# AVR_Programmer.net
KiCad netlist of a schematic drawn in Altium Designer
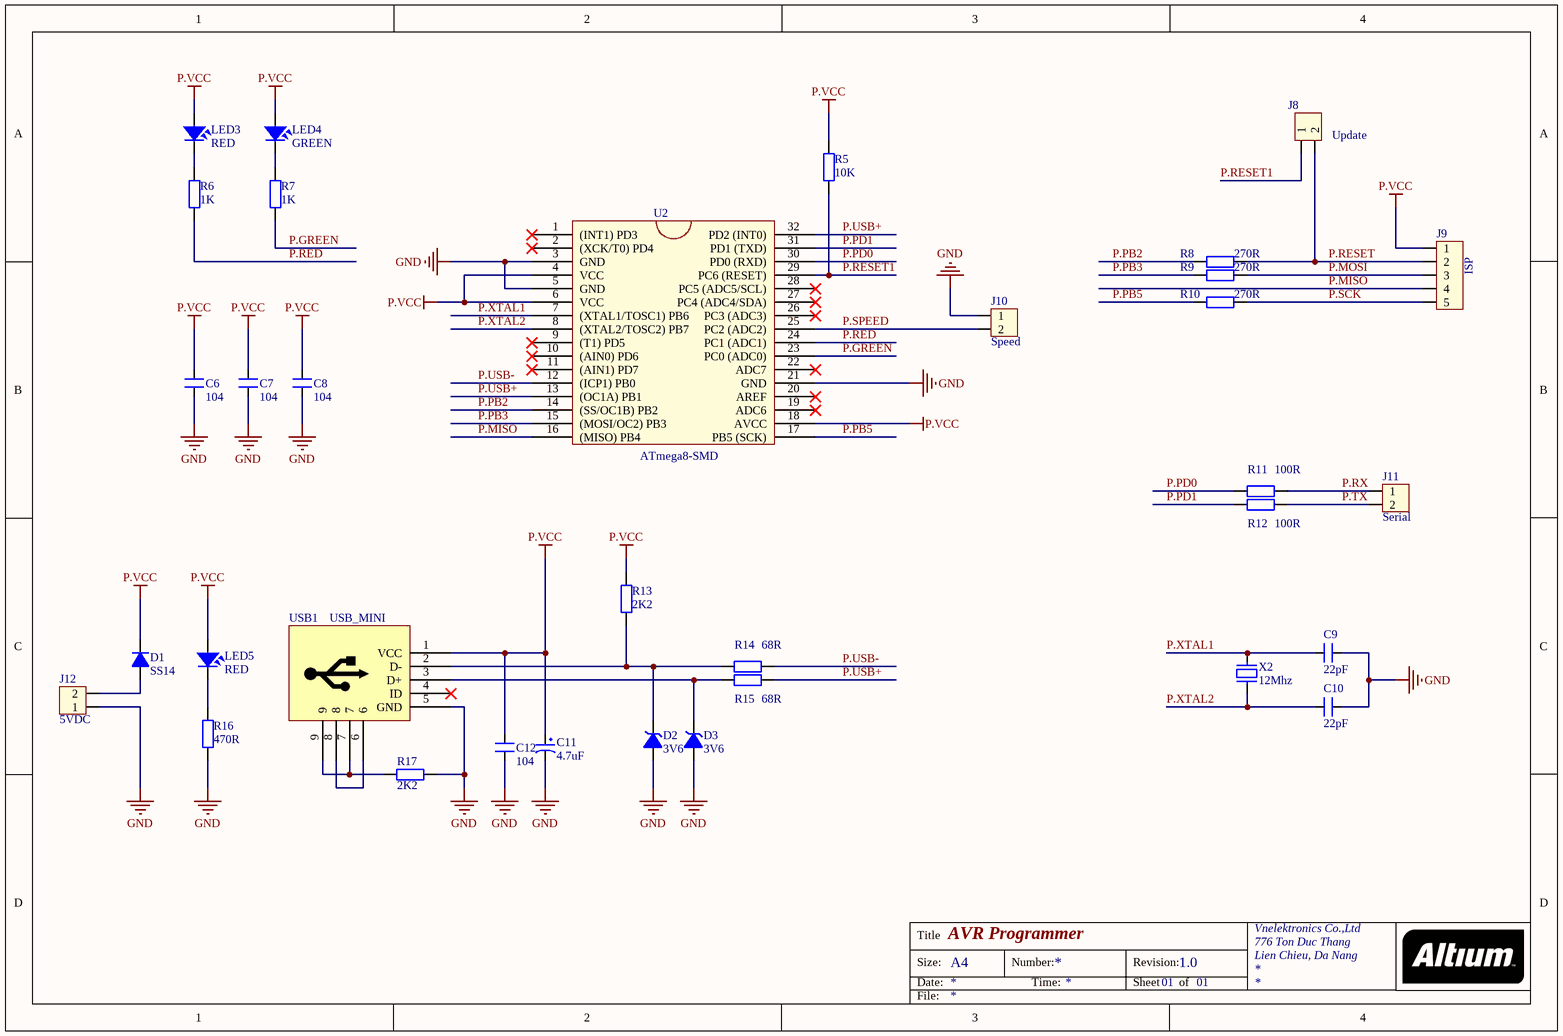
[diagram p0: AVR Programmer.SchDoc]

(export (version "E")
  (design (tool "Eeschema 10.0.6"))
  (components
    (comp (ref "C6")
      (value "104")
      (footprint "C0805")
      (description "Cap np 104 => 105pF")
      (libsource (lib "syhaunguyen") (part "CN2"))
    )
    (comp (ref "C7")
      (value "104")
      (footprint "C0805")
      (description "Cap np 104 => 105pF")
      (libsource (lib "syhaunguyen") (part "CN2"))
    )
    (comp (ref "C8")
      (value "104")
      (footprint "C0805")
      (description "Cap np 104 => 105pF")
      (libsource (lib "syhaunguyen") (part "CN2"))
    )
    (comp (ref "C9")
      (value "22pF")
      (footprint "C0603")
      (description "Cap np  1pF - 472pF")
      (libsource (lib "syhaunguyen") (part "CN1"))
    )
    (comp (ref "C10")
      (value "22pF")
      (footprint "C0603")
      (description "Cap np  1pF - 472pF")
      (libsource (lib "syhaunguyen") (part "CN1"))
    )
    (comp (ref "C11")
      (value "4.7uF")
      (footprint "C1210")
      (description "Cap P  0,1uF < 22uF , 16 - 50V")
      (libsource (lib "syhaunguyen") (part "CP1"))
    )
    (comp (ref "C12")
      (value "104")
      (footprint "C0805")
      (description "Cap np 104 => 105pF")
      (libsource (lib "syhaunguyen") (part "CN2"))
    )
    (comp (ref "D1")
      (value "SS14")
      (footprint "SS14")
      (description "Diode 1A")
      (libsource (lib "syhaunguyen") (part "D1A"))
    )
    (comp (ref "D2")
      (value "3V6")
      (footprint "1N5226")
      (description "Diode Zenner")
      (libsource (lib "syhaunguyen") (part "DZ"))
    )
    (comp (ref "D3")
      (value "3V6")
      (footprint "1N5226")
      (description "Diode Zenner")
      (libsource (lib "syhaunguyen") (part "DZ"))
    )
    (comp (ref "J8")
      (value "Update")
      (footprint "Header_2")
      (description "Header 2 (Green)")
      (libsource (lib "syhaunguyen") (part "Hed2"))
    )
    (comp (ref "J9")
      (value "ISP")
      (footprint "Header_5")
      (description "Header 5 (Green)")
      (libsource (lib "Tran Tuan") (part "Hed5"))
    )
    (comp (ref "J10")
      (value "Speed")
      (footprint "Header_2")
      (description "Header 2 (Green)")
      (libsource (lib "") (part "Hed2_1"))
    )
    (comp (ref "J11")
      (value "Serial")
      (footprint "Header_2")
      (description "Header 2 (Green)")
      (libsource (lib "") (part "Hed2_1"))
    )
    (comp (ref "J12")
      (value "5VDC")
      (footprint "Header_2")
      (description "Header 2 (Green)")
      (libsource (lib "") (part "Hed2_2"))
    )
    (comp (ref "LED3")
      (value "RED")
      (footprint "Led 0805R")
      (description "LED Single colour Green and Red")
      (libsource (lib "syhaunguyen") (part "LED"))
    )
    (comp (ref "LED4")
      (value "GREEN")
      (footprint "Led 0805G")
      (description "LED Single colour Green and Red")
      (libsource (lib "syhaunguyen") (part "LED"))
    )
    (comp (ref "LED5")
      (value "RED")
      (footprint "Led 0805R")
      (description "LED Single colour Green and Red")
      (libsource (lib "syhaunguyen") (part "LED"))
    )
    (comp (ref "R5")
      (value "10K")
      (footprint "RESC2012(0805)")
      (description "Resistor")
      (fields (field (name "Comment") "Res2") (field (name "PUBLISHER") "Altium Limited"))
      (libsource (lib "") (part "Res2_1"))
    )
    (comp (ref "R6")
      (value "1K")
      (footprint "RESC2012(0805)")
      (description "Resistor")
      (fields (field (name "Comment") "Res2") (field (name "PUBLISHER") "Altium Limited"))
      (libsource (lib "") (part "Res2_2"))
    )
    (comp (ref "R7")
      (value "1K")
      (footprint "RESC2012(0805)")
      (description "Resistor")
      (fields (field (name "Comment") "Res2") (field (name "PUBLISHER") "Altium Limited"))
      (libsource (lib "") (part "Res2_2"))
    )
    (comp (ref "R8")
      (value "270R")
      (footprint "RESC2012(0805)")
      (description "Resistor")
      (fields (field (name "Comment") "Res2") (field (name "PUBLISHER") "Altium Limited"))
      (libsource (lib "") (part "Res2_3"))
    )
    (comp (ref "R9")
      (value "270R")
      (footprint "RESC2012(0805)")
      (description "Resistor")
      (fields (field (name "Comment") "Res2") (field (name "PUBLISHER") "Altium Limited"))
      (libsource (lib "") (part "Res2_3"))
    )
    (comp (ref "R10")
      (value "270R")
      (footprint "RESC2012(0805)")
      (description "Resistor")
      (fields (field (name "Comment") "Res2") (field (name "PUBLISHER") "Altium Limited"))
      (libsource (lib "") (part "Res2_3"))
    )
    (comp (ref "R11")
      (value "100R")
      (footprint "RESC2012(0805)")
      (description "Resistor")
      (fields (field (name "Comment") "Res2") (field (name "PUBLISHER") "Altium Limited"))
      (libsource (lib "") (part "Res2_3"))
    )
    (comp (ref "R12")
      (value "100R")
      (footprint "RESC2012(0805)")
      (description "Resistor")
      (fields (field (name "Comment") "Res2") (field (name "PUBLISHER") "Altium Limited"))
      (libsource (lib "") (part "Res2_3"))
    )
    (comp (ref "R13")
      (value "2K2")
      (footprint "RESC2012(0805)")
      (description "Resistor")
      (fields (field (name "Comment") "Res2") (field (name "PUBLISHER") "Altium Limited"))
      (libsource (lib "") (part "Res2_2"))
    )
    (comp (ref "R14")
      (value "68R")
      (footprint "RESC2012(0805)")
      (description "Resistor")
      (fields (field (name "Comment") "Res2") (field (name "PUBLISHER") "Altium Limited"))
      (libsource (lib "Miscellaneous Devices") (part "Res2"))
    )
    (comp (ref "R15")
      (value "68R")
      (footprint "RESC2012(0805)")
      (description "Resistor")
      (fields (field (name "Comment") "Res2") (field (name "PUBLISHER") "Altium Limited"))
      (libsource (lib "Miscellaneous Devices") (part "Res2"))
    )
    (comp (ref "R16")
      (value "470R")
      (footprint "RESC2012(0805)")
      (description "Resistor")
      (fields (field (name "Comment") "Res2") (field (name "PUBLISHER") "Altium Limited"))
      (libsource (lib "") (part "Res2_2"))
    )
    (comp (ref "R17")
      (value "2K2")
      (footprint "RESC2012(0805)")
      (description "Resistor")
      (fields (field (name "Comment") "Res2") (field (name "PUBLISHER") "Altium Limited"))
      (libsource (lib "") (part "Res2_3"))
    )
    (comp (ref "U2")
      (value "ATmega8-SMD")
      (footprint "ATMEGA_8_SMD")
      (description "High-performance, Low-power Atmel  ®  AVR  ®   8-bit Microcontroller")
      (libsource (lib "AT8") (part "ATmega8_SMD_32pin"))
    )
    (comp (ref "USB1") (value "USB_MINI") (footprint "USBMNIB") (libsource (lib "lpson") (part "USB_MINI")))
    (comp (ref "X2")
      (value "12Mhz")
      (footprint "CRYSTAL")
      (description "Crystal For all Crystal 2pin.")
      (libsource (lib "syhaunguyen") (part "XT2"))
    )
  )
  (nets
    (net (code "1") (name "/P.GREEN") (class "Default")
      (node (ref "R7") (pin "2") (pinfunction "2_2") (pintype "passive"))
      (node (ref "U2") (pin "23") (pinfunction "PC0_(ADC0)_23") (pintype "passive"))
    )
    (net (code "2") (name "/P.MISO") (class "Default")
      (node (ref "J9") (pin "4") (pinfunction "4_4") (pintype "passive"))
      (node (ref "U2") (pin "16") (pinfunction "(MISO)_PB4_16") (pintype "passive"))
    )
    (net (code "3") (name "/P.MOSI") (class "Default")
      (node (ref "J9") (pin "3") (pinfunction "3_3") (pintype "passive"))
      (node (ref "R9") (pin "2") (pinfunction "2_2") (pintype "passive"))
    )
    (net (code "4") (name "/P.PB2") (class "Default")
      (node (ref "R8") (pin "1") (pinfunction "1_1") (pintype "passive"))
      (node (ref "U2") (pin "14") (pinfunction "(SS/OC1B)_PB2_14") (pintype "passive"))
    )
    (net (code "5") (name "/P.PB3") (class "Default")
      (node (ref "R9") (pin "1") (pinfunction "1_1") (pintype "passive"))
      (node (ref "U2") (pin "15") (pinfunction "(MOSI/OC2)_PB3_15") (pintype "passive"))
    )
    (net (code "6") (name "/P.PB5") (class "Default")
      (node (ref "R10") (pin "1") (pinfunction "1_1") (pintype "passive"))
      (node (ref "U2") (pin "17") (pinfunction "PB5_(SCK)_17") (pintype "passive"))
    )
    (net (code "7") (name "/P.PD0") (class "Default")
      (node (ref "R11") (pin "1") (pinfunction "1_1") (pintype "passive"))
      (node (ref "U2") (pin "30") (pinfunction "PD0_(RXD)_30") (pintype "passive"))
    )
    (net (code "8") (name "/P.PD1") (class "Default")
      (node (ref "R12") (pin "1") (pinfunction "1_1") (pintype "passive"))
      (node (ref "U2") (pin "31") (pinfunction "PD1_(TXD)_31") (pintype "passive"))
    )
    (net (code "9") (name "/P.RED") (class "Default")
      (node (ref "R6") (pin "2") (pinfunction "2_2") (pintype "passive"))
      (node (ref "U2") (pin "24") (pinfunction "PC1_(ADC1)_24") (pintype "passive"))
    )
    (net (code "10") (name "/P.RESET") (class "Default")
      (node (ref "J8") (pin "2") (pinfunction "2_2") (pintype "passive"))
      (node (ref "J9") (pin "2") (pinfunction "2_2") (pintype "passive"))
      (node (ref "R8") (pin "2") (pinfunction "2_2") (pintype "passive"))
    )
    (net (code "11") (name "/P.RESET1") (class "Default")
      (node (ref "J8") (pin "1") (pinfunction "1_1") (pintype "passive"))
      (node (ref "R5") (pin "1") (pinfunction "1_1") (pintype "passive"))
      (node (ref "U2") (pin "29") (pinfunction "PC6_(RESET)_29") (pintype "passive"))
    )
    (net (code "12") (name "/P.RX") (class "Default")
      (node (ref "J11") (pin "1") (pinfunction "1_1") (pintype "passive"))
      (node (ref "R11") (pin "2") (pinfunction "2_2") (pintype "passive"))
    )
    (net (code "13") (name "/P.SCK") (class "Default")
      (node (ref "J9") (pin "5") (pinfunction "5_5") (pintype "passive"))
      (node (ref "R10") (pin "2") (pinfunction "2_2") (pintype "passive"))
    )
    (net (code "14") (name "/P.SPEED") (class "Default")
      (node (ref "J10") (pin "2") (pinfunction "2_2") (pintype "passive"))
      (node (ref "U2") (pin "25") (pinfunction "PC2_(ADC2)_25") (pintype "passive"))
    )
    (net (code "15") (name "/P.TX") (class "Default")
      (node (ref "J11") (pin "2") (pinfunction "2_2") (pintype "passive"))
      (node (ref "R12") (pin "2") (pinfunction "2_2") (pintype "passive"))
    )
    (net (code "16") (name "/P.USB+") (class "Default")
      (node (ref "R15") (pin "1") (pinfunction "1_1") (pintype "passive"))
      (node (ref "U2") (pin "13") (pinfunction "(OC1A)_PB1_13") (pintype "passive"))
      (node (ref "U2") (pin "32") (pinfunction "PD2_(INT0)_32") (pintype "passive"))
    )
    (net (code "17") (name "/P.USB-") (class "Default")
      (node (ref "R14") (pin "1") (pinfunction "1_1") (pintype "passive"))
      (node (ref "U2") (pin "12") (pinfunction "(ICP1)_PB0_12") (pintype "passive"))
    )
    (net (code "18") (name "/P.XTAL1") (class "Default")
      (node (ref "C9") (pin "2") (pinfunction "2_2") (pintype "passive"))
      (node (ref "U2") (pin "7") (pinfunction "(XTAL1/TOSC1)_PB6_7") (pintype "passive"))
      (node (ref "X2") (pin "1") (pinfunction "1_1") (pintype "passive"))
    )
    (net (code "19") (name "/P.XTAL2") (class "Default")
      (node (ref "C10") (pin "2") (pinfunction "2_2") (pintype "passive"))
      (node (ref "U2") (pin "8") (pinfunction "(XTAL2/TOSC2)_PB7_8") (pintype "passive"))
      (node (ref "X2") (pin "2") (pinfunction "2_2") (pintype "passive"))
    )
    (net (code "20") (name "GND") (class "Default")
      (node (ref "C10") (pin "1") (pinfunction "1_1") (pintype "passive"))
      (node (ref "C11") (pin "2") (pinfunction "2_2") (pintype "passive"))
      (node (ref "C12") (pin "1") (pinfunction "1_1") (pintype "passive"))
      (node (ref "C6") (pin "1") (pinfunction "1_1") (pintype "passive"))
      (node (ref "C7") (pin "1") (pinfunction "1_1") (pintype "passive"))
      (node (ref "C8") (pin "1") (pinfunction "1_1") (pintype "passive"))
      (node (ref "C9") (pin "1") (pinfunction "1_1") (pintype "passive"))
      (node (ref "D2") (pin "1") (pinfunction "A_1") (pintype "passive"))
      (node (ref "D3") (pin "1") (pinfunction "A_1") (pintype "passive"))
      (node (ref "J10") (pin "1") (pinfunction "1_1") (pintype "passive"))
      (node (ref "J12") (pin "1") (pinfunction "1_1") (pintype "passive"))
      (node (ref "R16") (pin "2") (pinfunction "2_2") (pintype "passive"))
      (node (ref "R17") (pin "2") (pinfunction "2_2") (pintype "passive"))
      (node (ref "U2") (pin "21") (pinfunction "GND_21") (pintype "passive"))
      (node (ref "U2") (pin "3") (pinfunction "GND_3") (pintype "passive"))
      (node (ref "U2") (pin "5") (pinfunction "GND_5") (pintype "passive"))
      (node (ref "USB1") (pin "5") (pinfunction "GND_5") (pintype "passive"))
    )
    (net (code "21") (name "Net-(D1-A)") (class "Default")
      (node (ref "D1") (pin "1") (pinfunction "A_1") (pintype "passive"))
      (node (ref "J12") (pin "2") (pinfunction "2_2") (pintype "passive"))
    )
    (net (code "22") (name "Net-(D2-K)") (class "Default")
      (node (ref "D2") (pin "2") (pinfunction "K_2") (pintype "passive"))
      (node (ref "R13") (pin "2") (pinfunction "2_2") (pintype "passive"))
      (node (ref "R14") (pin "2") (pinfunction "2_2") (pintype "passive"))
      (node (ref "USB1") (pin "2") (pinfunction "D-_2") (pintype "passive"))
    )
    (net (code "23") (name "Net-(D3-K)") (class "Default")
      (node (ref "D3") (pin "2") (pinfunction "K_2") (pintype "passive"))
      (node (ref "R15") (pin "2") (pinfunction "2_2") (pintype "passive"))
      (node (ref "USB1") (pin "3") (pinfunction "D+_3") (pintype "passive"))
    )
    (net (code "24") (name "Net-(LED3-Pad2)") (class "Default")
      (node (ref "LED3") (pin "2") (pinfunction "2_2") (pintype "passive"))
      (node (ref "R6") (pin "1") (pinfunction "1_1") (pintype "passive"))
    )
    (net (code "25") (name "Net-(LED4-Pad2)") (class "Default")
      (node (ref "LED4") (pin "2") (pinfunction "2_2") (pintype "passive"))
      (node (ref "R7") (pin "1") (pinfunction "1_1") (pintype "passive"))
    )
    (net (code "26") (name "Net-(LED5-Pad2)") (class "Default")
      (node (ref "LED5") (pin "2") (pinfunction "2_2") (pintype "passive"))
      (node (ref "R16") (pin "1") (pinfunction "1_1") (pintype "passive"))
    )
    (net (code "27") (name "Net-(R17-Pad1)") (class "Default")
      (node (ref "R17") (pin "1") (pinfunction "1_1") (pintype "passive"))
      (node (ref "USB1") (pin "7") (pinfunction "7_7") (pintype "passive"))
      (node (ref "USB1") (pin "9") (pinfunction "9_9") (pintype "passive"))
    )
    (net (code "28") (name "Net-(USB1-Pad6)") (class "Default")
      (node (ref "USB1") (pin "6") (pinfunction "6_6") (pintype "passive"))
      (node (ref "USB1") (pin "8") (pinfunction "8_8") (pintype "passive"))
    )
    (net (code "29") (name "P.VCC") (class "Default")
      (node (ref "C11") (pin "1") (pinfunction "1_1") (pintype "passive"))
      (node (ref "C12") (pin "2") (pinfunction "2_2") (pintype "passive"))
      (node (ref "C6") (pin "2") (pinfunction "2_2") (pintype "passive"))
      (node (ref "C7") (pin "2") (pinfunction "2_2") (pintype "passive"))
      (node (ref "C8") (pin "2") (pinfunction "2_2") (pintype "passive"))
      (node (ref "D1") (pin "2") (pinfunction "K_2") (pintype "passive"))
      (node (ref "J9") (pin "1") (pinfunction "1_1") (pintype "passive"))
      (node (ref "LED3") (pin "1") (pinfunction "1_1") (pintype "passive"))
      (node (ref "LED4") (pin "1") (pinfunction "1_1") (pintype "passive"))
      (node (ref "LED5") (pin "1") (pinfunction "1_1") (pintype "passive"))
      (node (ref "R13") (pin "1") (pinfunction "1_1") (pintype "passive"))
      (node (ref "R5") (pin "2") (pinfunction "2_2") (pintype "passive"))
      (node (ref "U2") (pin "18") (pinfunction "AVCC_18") (pintype "passive"))
      (node (ref "U2") (pin "4") (pinfunction "VCC_4") (pintype "passive"))
      (node (ref "U2") (pin "6") (pinfunction "VCC_6") (pintype "passive"))
      (node (ref "USB1") (pin "1") (pinfunction "VCC_1") (pintype "passive"))
    )
    (net (code "30") (name "unconnected-(U2-(AIN0)_PD6-Pad10)") (class "Default")
      (node (ref "U2") (pin "10") (pinfunction "(AIN0)_PD6_10") (pintype "passive+no_connect"))
    )
    (net (code "31") (name "unconnected-(U2-(AIN1)_PD7-Pad11)") (class "Default")
      (node (ref "U2") (pin "11") (pinfunction "(AIN1)_PD7_11") (pintype "passive+no_connect"))
    )
    (net (code "32") (name "unconnected-(U2-(INT1)_PD3-Pad1)") (class "Default")
      (node (ref "U2") (pin "1") (pinfunction "(INT1)_PD3_1") (pintype "passive+no_connect"))
    )
    (net (code "33") (name "unconnected-(U2-(T1)_PD5-Pad9)") (class "Default")
      (node (ref "U2") (pin "9") (pinfunction "(T1)_PD5_9") (pintype "passive+no_connect"))
    )
    (net (code "34") (name "unconnected-(U2-(XCK{slash}T0)_PD4-Pad2)") (class "Default")
      (node (ref "U2") (pin "2") (pinfunction "(XCK/T0)_PD4_2") (pintype "passive+no_connect"))
    )
    (net (code "35") (name "unconnected-(U2-ADC6-Pad19)") (class "Default")
      (node (ref "U2") (pin "19") (pinfunction "ADC6_19") (pintype "passive+no_connect"))
    )
    (net (code "36") (name "unconnected-(U2-ADC7-Pad22)") (class "Default")
      (node (ref "U2") (pin "22") (pinfunction "ADC7_22") (pintype "passive+no_connect"))
    )
    (net (code "37") (name "unconnected-(U2-AREF-Pad20)") (class "Default")
      (node (ref "U2") (pin "20") (pinfunction "AREF_20") (pintype "passive+no_connect"))
    )
    (net (code "38") (name "unconnected-(U2-PC3_(ADC3)-Pad26)") (class "Default")
      (node (ref "U2") (pin "26") (pinfunction "PC3_(ADC3)_26") (pintype "passive+no_connect"))
    )
    (net (code "39") (name "unconnected-(U2-PC4_(ADC4{slash}SDA)-Pad27)") (class "Default")
      (node (ref "U2") (pin "27") (pinfunction "PC4_(ADC4/SDA)_27") (pintype "passive+no_connect"))
    )
    (net (code "40") (name "unconnected-(U2-PC5_(ADC5{slash}SCL)-Pad28)") (class "Default")
      (node (ref "U2") (pin "28") (pinfunction "PC5_(ADC5/SCL)_28") (pintype "passive+no_connect"))
    )
    (net (code "41") (name "unconnected-(USB1-ID-Pad4)") (class "Default")
      (node (ref "USB1") (pin "4") (pinfunction "ID_4") (pintype "passive+no_connect"))
    )
  )
)
